# MIDDLE_LAYER.net
KiCad netlist of a schematic drawn in Altium Designer
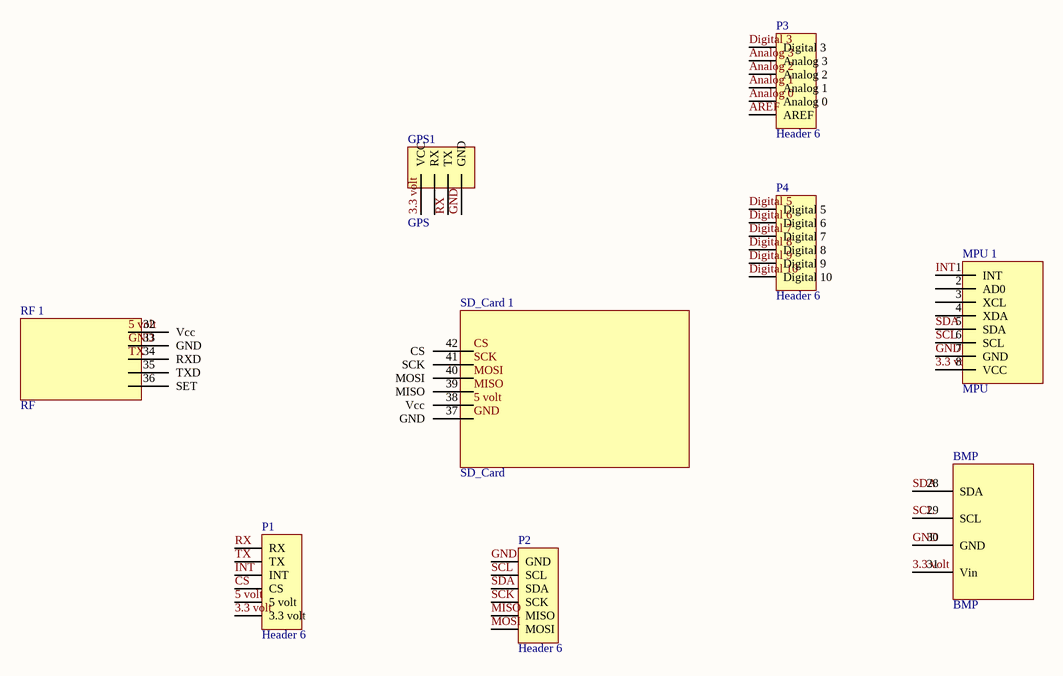
[diagram p0: MIDDLE LAYER.SchDoc]

(export (version "E")
  (design (tool "Eeschema 10.0.6"))
  (components
    (comp (ref "BMP") (value "BMP") (footprint "BMP") (libsource (lib "bmb") (part "BMP")))
    (comp (ref "GPS1") (value "GPS") (footprint "GPS") (libsource (lib "GPS") (part "GPS")))
    (comp (ref "MPU 1") (value "MPU") (footprint "MPU") (libsource (lib "MPU") (part "MPU")))
    (comp (ref "P1")
      (value "Header 6")
      (footprint "HDR1X6")
      (description "Header, 6-Pin")
      (fields (field (name "PUBLISHER") "Altium Limited"))
      (libsource (lib "Miscellaneous Connectors") (part "Header 6"))
    )
    (comp (ref "P2")
      (value "Header 6")
      (footprint "HDR1X6")
      (description "Header, 6-Pin")
      (fields (field (name "PUBLISHER") "Altium Limited"))
      (libsource (lib "Miscellaneous Connectors") (part "Header 6"))
    )
    (comp (ref "P3")
      (value "Header 6")
      (footprint "HDR1X6")
      (description "Header, 6-Pin")
      (fields (field (name "PUBLISHER") "Altium Limited"))
      (libsource (lib "Miscellaneous Connectors") (part "Header 6"))
    )
    (comp (ref "P4")
      (value "Header 6")
      (footprint "HDR1X6")
      (description "Header, 6-Pin")
      (fields (field (name "PUBLISHER") "Altium Limited"))
      (libsource (lib "Miscellaneous Connectors") (part "Header 6"))
    )
    (comp (ref "RF 1") (value "RF") (footprint "RF") (libsource (lib "RF") (part "RF")))
    (comp (ref "SD_Card 1")
      (value "SD_Card")
      (footprint "SD_Card")
      (libsource (lib "SD_Card") (part "SD_Card"))
    )
  )
  (nets
    (net (code "1") (name "/3.3 volt") (class "Default")
      (node (ref "BMP") (pin "31") (pinfunction "Vin_31") (pintype "passive"))
      (node (ref "GPS1") (pin "12") (pinfunction "VCC_12") (pintype "passive"))
      (node (ref "MPU 1") (pin "8") (pinfunction "VCC_8") (pintype "passive"))
      (node (ref "P1") (pin "6") (pinfunction "3.3_volt_6") (pintype "passive"))
    )
    (net (code "2") (name "/5 volt") (class "Default")
      (node (ref "P1") (pin "5") (pinfunction "5_volt_5") (pintype "passive"))
      (node (ref "RF 1") (pin "32") (pinfunction "Vcc_32") (pintype "passive"))
      (node (ref "SD_Card 1") (pin "38") (pinfunction "Vcc_38") (pintype "passive"))
    )
    (net (code "3") (name "/AREF") (class "Default")
      (node (ref "P3") (pin "6") (pinfunction "3.3_volt_6") (pintype "passive"))
    )
    (net (code "4") (name "/Analog 0") (class "Default")
      (node (ref "P3") (pin "5") (pinfunction "5_volt_5") (pintype "passive"))
    )
    (net (code "5") (name "/Analog 1") (class "Default")
      (node (ref "P3") (pin "4") (pinfunction "CS_4") (pintype "passive"))
    )
    (net (code "6") (name "/Analog 2") (class "Default")
      (node (ref "P3") (pin "3") (pinfunction "INT_3") (pintype "passive"))
    )
    (net (code "7") (name "/Analog 3") (class "Default")
      (node (ref "P3") (pin "2") (pinfunction "TX_2") (pintype "passive"))
    )
    (net (code "8") (name "/CS") (class "Default")
      (node (ref "P1") (pin "4") (pinfunction "CS_4") (pintype "passive"))
      (node (ref "SD_Card 1") (pin "42") (pinfunction "CS_42") (pintype "passive"))
    )
    (net (code "9") (name "/Digital 3") (class "Default")
      (node (ref "P3") (pin "1") (pinfunction "RX_1") (pintype "passive"))
    )
    (net (code "10") (name "/Digital 5") (class "Default")
      (node (ref "P4") (pin "1") (pinfunction "RX_1") (pintype "passive"))
    )
    (net (code "11") (name "/Digital 6") (class "Default")
      (node (ref "P4") (pin "2") (pinfunction "TX_2") (pintype "passive"))
    )
    (net (code "12") (name "/Digital 7") (class "Default")
      (node (ref "P4") (pin "3") (pinfunction "INT_3") (pintype "passive"))
    )
    (net (code "13") (name "/Digital 8") (class "Default")
      (node (ref "P4") (pin "4") (pinfunction "CS_4") (pintype "passive"))
    )
    (net (code "14") (name "/Digital 9") (class "Default")
      (node (ref "P4") (pin "5") (pinfunction "5_volt_5") (pintype "passive"))
    )
    (net (code "15") (name "/Digital 10") (class "Default")
      (node (ref "P4") (pin "6") (pinfunction "3.3_volt_6") (pintype "passive"))
    )
    (net (code "16") (name "/GND") (class "Default")
      (node (ref "BMP") (pin "30") (pinfunction "GND_30") (pintype "passive"))
      (node (ref "GPS1") (pin "15") (pinfunction "GND_15") (pintype "passive"))
      (node (ref "MPU 1") (pin "7") (pinfunction "GND_7") (pintype "passive"))
      (node (ref "P2") (pin "1") (pinfunction "RX_1") (pintype "passive"))
      (node (ref "RF 1") (pin "33") (pinfunction "GND_33") (pintype "passive"))
      (node (ref "SD_Card 1") (pin "37") (pinfunction "GND_37") (pintype "passive"))
    )
    (net (code "17") (name "/INT") (class "Default")
      (node (ref "MPU 1") (pin "1") (pinfunction "INT_1") (pintype "passive"))
      (node (ref "P1") (pin "3") (pinfunction "INT_3") (pintype "passive"))
    )
    (net (code "18") (name "/MISO") (class "Default")
      (node (ref "P2") (pin "5") (pinfunction "5_volt_5") (pintype "passive"))
      (node (ref "SD_Card 1") (pin "39") (pinfunction "MISO_39") (pintype "passive"))
    )
    (net (code "19") (name "/MOSI") (class "Default")
      (node (ref "P2") (pin "6") (pinfunction "3.3_volt_6") (pintype "passive"))
      (node (ref "SD_Card 1") (pin "40") (pinfunction "MOSI_40") (pintype "passive"))
    )
    (net (code "20") (name "/RX") (class "Default")
      (node (ref "GPS1") (pin "14") (pinfunction "TX_14") (pintype "passive"))
      (node (ref "P1") (pin "1") (pinfunction "RX_1") (pintype "passive"))
    )
    (net (code "21") (name "/SCK") (class "Default")
      (node (ref "P2") (pin "4") (pinfunction "CS_4") (pintype "passive"))
      (node (ref "SD_Card 1") (pin "41") (pinfunction "SCK_41") (pintype "passive"))
    )
    (net (code "22") (name "/SCL") (class "Default")
      (node (ref "BMP") (pin "29") (pinfunction "SCL_29") (pintype "passive"))
      (node (ref "MPU 1") (pin "6") (pinfunction "SCL_6") (pintype "passive"))
      (node (ref "P2") (pin "2") (pinfunction "TX_2") (pintype "passive"))
    )
    (net (code "23") (name "/SDA") (class "Default")
      (node (ref "BMP") (pin "28") (pinfunction "SDA_28") (pintype "passive"))
      (node (ref "MPU 1") (pin "5") (pinfunction "SDA_5") (pintype "passive"))
      (node (ref "P2") (pin "3") (pinfunction "INT_3") (pintype "passive"))
    )
    (net (code "24") (name "/TX") (class "Default")
      (node (ref "P1") (pin "2") (pinfunction "TX_2") (pintype "passive"))
      (node (ref "RF 1") (pin "34") (pinfunction "RXD_34") (pintype "passive"))
    )
    (net (code "25") (name "unconnected-(GPS1-RX-Pad13)") (class "Default")
      (node (ref "GPS1") (pin "13") (pinfunction "RX_13") (pintype "passive"))
    )
    (net (code "26") (name "unconnected-(MPU 1-AD0-Pad2)") (class "Default")
      (node (ref "MPU 1") (pin "2") (pinfunction "AD0_2") (pintype "passive"))
    )
    (net (code "27") (name "unconnected-(MPU 1-XCL-Pad3)") (class "Default")
      (node (ref "MPU 1") (pin "3") (pinfunction "XCL_3") (pintype "passive"))
    )
    (net (code "28") (name "unconnected-(MPU 1-XDA-Pad4)") (class "Default")
      (node (ref "MPU 1") (pin "4") (pinfunction "XDA_4") (pintype "passive"))
    )
    (net (code "29") (name "unconnected-(RF 1-SET-Pad36)") (class "Default")
      (node (ref "RF 1") (pin "36") (pinfunction "SET_36") (pintype "passive"))
    )
    (net (code "30") (name "unconnected-(RF 1-TXD-Pad35)") (class "Default")
      (node (ref "RF 1") (pin "35") (pinfunction "TXD_35") (pintype "passive"))
    )
  )
)
